# KKK_valdiklis_v3.net
KiCad netlist of a schematic drawn in EAGLE
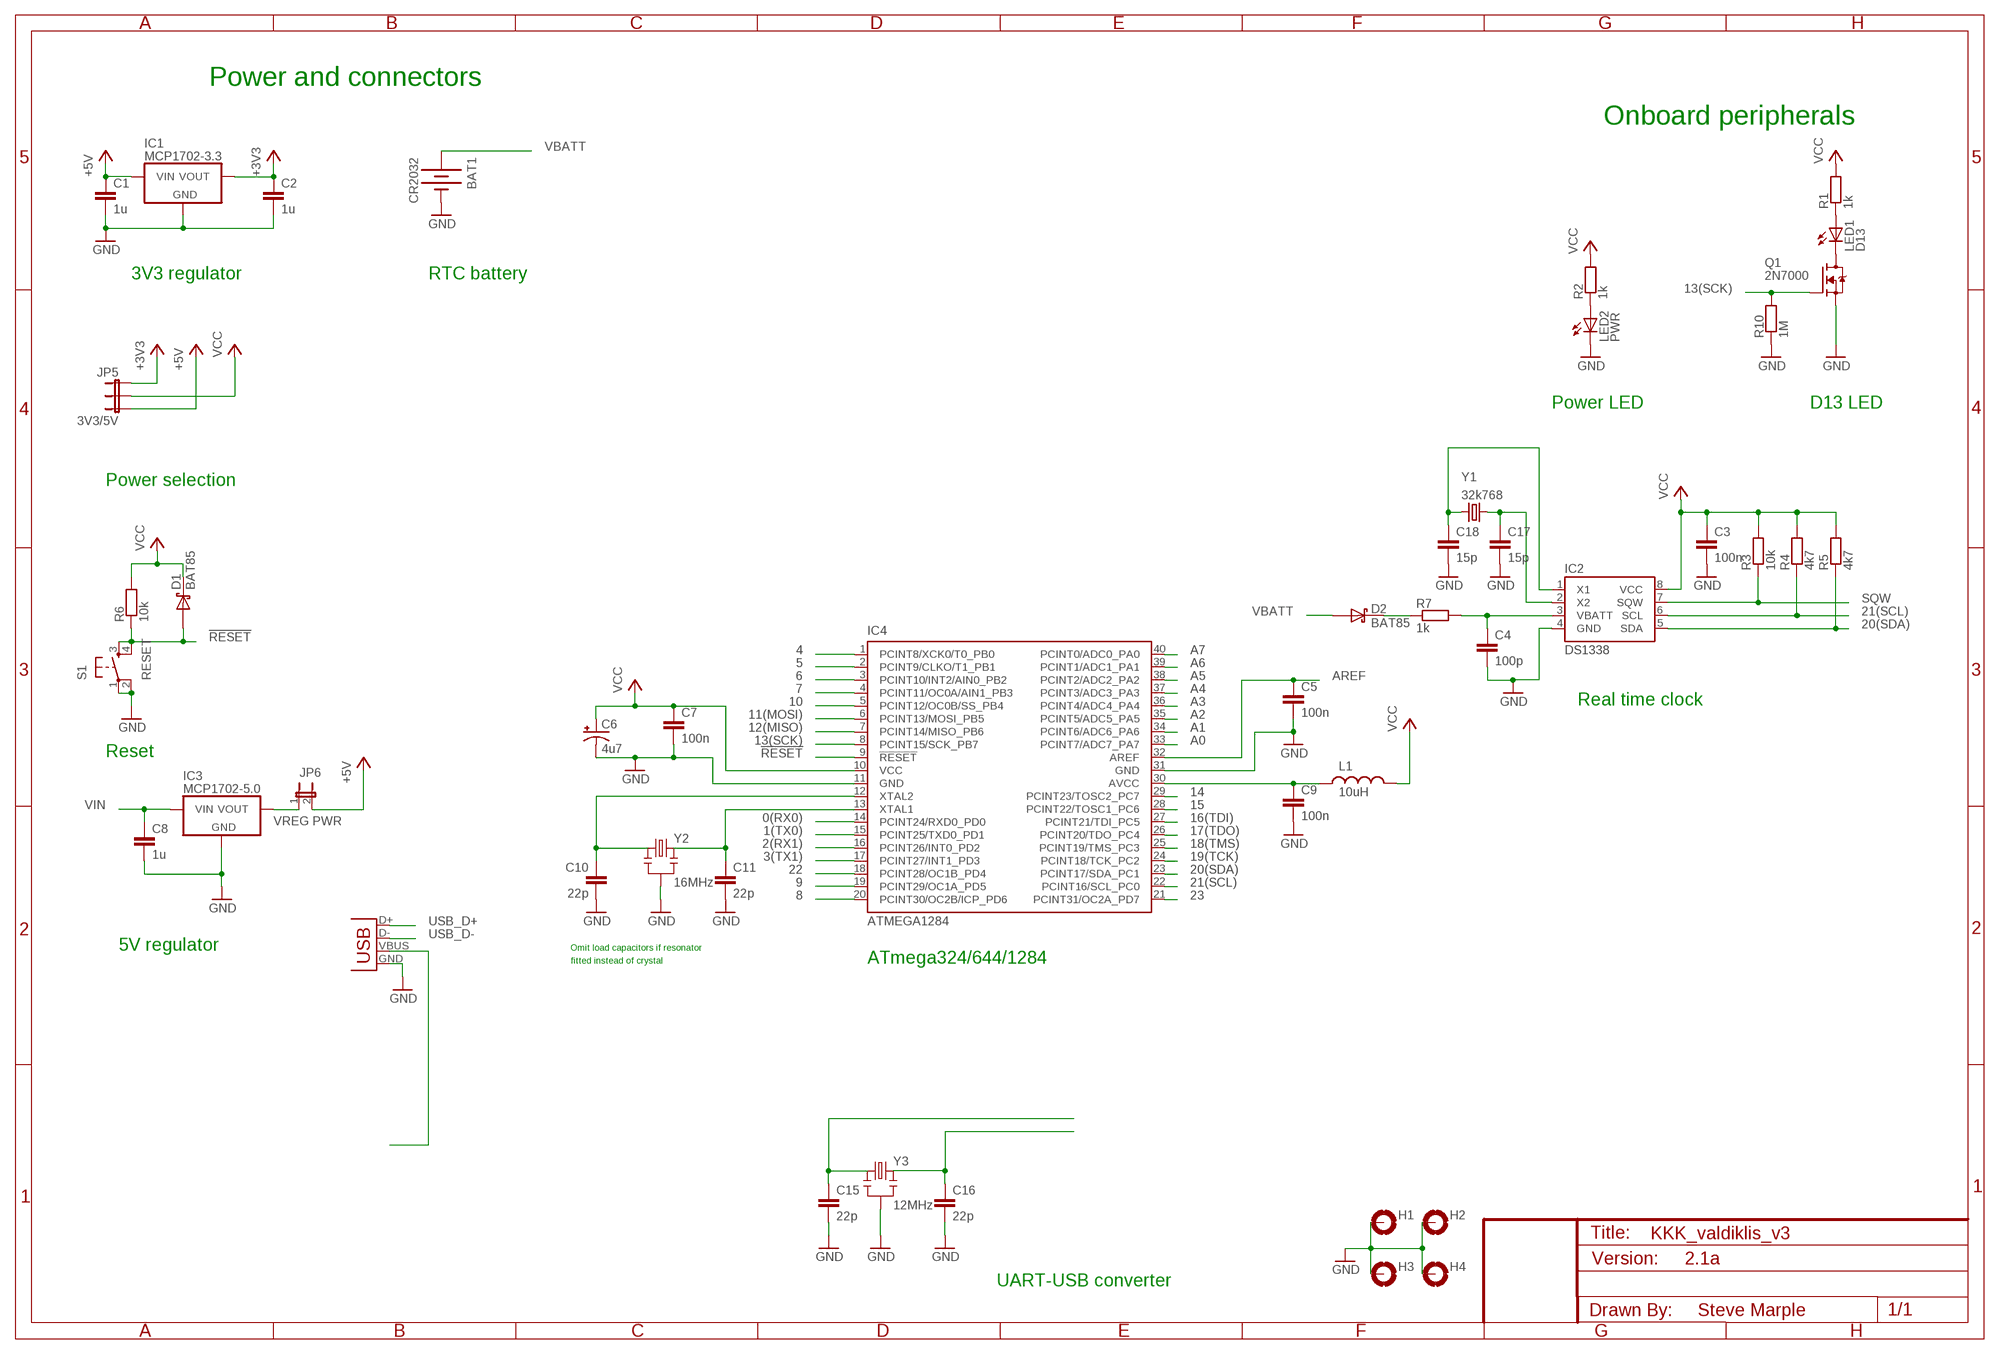
[diagram p0: schematic, sheet 1]

(export (version "E")
  (design (tool "Eeschema 10.0.6"))
  (components
    (comp (ref "BAT1")
      (value "CR2032")
      (footprint "eagle-import:BATTCOM_20MM_PTH")
      (libsource (lib "eagle-import") (part "BATTERY20PTH"))
    )
    (comp (ref "C1")
      (value "1u")
      (footprint "eagle-import:CAP-PTH-5MM")
      (libsource (lib "eagle-import") (part "CAPPTH1"))
    )
    (comp (ref "C2")
      (value "1u")
      (footprint "eagle-import:CAP-PTH-5MM")
      (libsource (lib "eagle-import") (part "CAPPTH1"))
    )
    (comp (ref "C3")
      (value "100n")
      (footprint "eagle-import:CAP-PTH-SMALL")
      (libsource (lib "eagle-import") (part "CAPPTH"))
    )
    (comp (ref "C4")
      (value "100p")
      (footprint "eagle-import:CAP-PTH-SMALL")
      (libsource (lib "eagle-import") (part "CAPPTH"))
    )
    (comp (ref "C5")
      (value "100n")
      (footprint "eagle-import:CAP-PTH-SMALL")
      (libsource (lib "eagle-import") (part "CAPPTH"))
    )
    (comp (ref "C6")
      (value "4u7")
      (footprint "eagle-import:CPOL-RADIAL-10UF-25V")
      (libsource (lib "eagle-import") (part "CAP_POLPTH2"))
    )
    (comp (ref "C7")
      (value "100n")
      (footprint "eagle-import:CAP-PTH-SMALL")
      (libsource (lib "eagle-import") (part "CAPPTH"))
    )
    (comp (ref "C8")
      (value "1u")
      (footprint "eagle-import:CAP-PTH-5MM")
      (libsource (lib "eagle-import") (part "CAPPTH1"))
    )
    (comp (ref "C9")
      (value "100n")
      (footprint "eagle-import:CAP-PTH-SMALL")
      (libsource (lib "eagle-import") (part "CAPPTH"))
    )
    (comp (ref "C10")
      (value "22p")
      (footprint "eagle-import:CAP-PTH-SMALL")
      (libsource (lib "eagle-import") (part "CAPPTH"))
    )
    (comp (ref "C11")
      (value "22p")
      (footprint "eagle-import:CAP-PTH-SMALL")
      (libsource (lib "eagle-import") (part "CAPPTH"))
    )
    (comp (ref "C15")
      (value "22p")
      (footprint "eagle-import:CAP-PTH-SMALL")
      (libsource (lib "eagle-import") (part "CAPPTH"))
    )
    (comp (ref "C16")
      (value "22p")
      (footprint "eagle-import:CAP-PTH-SMALL")
      (libsource (lib "eagle-import") (part "CAPPTH"))
    )
    (comp (ref "C17")
      (value "15p")
      (footprint "eagle-import:CAP-PTH-SMALL")
      (libsource (lib "eagle-import") (part "CAPPTH"))
    )
    (comp (ref "C18")
      (value "15p")
      (footprint "eagle-import:CAP-PTH-SMALL")
      (libsource (lib "eagle-import") (part "CAPPTH"))
    )
    (comp (ref "D1")
      (value "BAT85")
      (footprint "eagle-import:DIODE-TH-0.4")
      (libsource (lib "eagle-import") (part "DIODE-SCHOTTKY"))
    )
    (comp (ref "D2")
      (value "BAT85")
      (footprint "eagle-import:DIODE-TH-0.4")
      (libsource (lib "eagle-import") (part "DIODE-SCHOTTKY"))
    )
    (comp (ref "H1")
      (value "MOUNT-PAD-ROUND3.0")
      (footprint "eagle-import:3,0-PAD")
      (libsource (lib "eagle-import") (part "MOUNT-PAD-ROUND3.0"))
    )
    (comp (ref "H2")
      (value "MOUNT-PAD-ROUND3.0")
      (footprint "eagle-import:3,0-PAD")
      (libsource (lib "eagle-import") (part "MOUNT-PAD-ROUND3.0"))
    )
    (comp (ref "H3")
      (value "MOUNT-PAD-ROUND3.0")
      (footprint "eagle-import:3,0-PAD")
      (libsource (lib "eagle-import") (part "MOUNT-PAD-ROUND3.0"))
    )
    (comp (ref "H4")
      (value "MOUNT-PAD-ROUND3.0")
      (footprint "eagle-import:3,0-PAD")
      (libsource (lib "eagle-import") (part "MOUNT-PAD-ROUND3.0"))
    )
    (comp (ref "IC1")
      (value "MCP1702-3.3")
      (footprint "eagle-import:TO-92")
      (libsource (lib "eagle-import") (part "MCP1702"))
    )
    (comp (ref "IC2")
      (value "DS1338")
      (footprint "eagle-import:SO08")
      (libsource (lib "eagle-import") (part "DS1307SO08"))
    )
    (comp (ref "IC3")
      (value "MCP1702-5.0")
      (footprint "eagle-import:TO-92")
      (libsource (lib "eagle-import") (part "MCP1702"))
    )
    (comp (ref "IC4")
      (value "ATMEGA1284")
      (footprint "eagle-import:DIL40")
      (fields (field (name "MPN") "ATMEGA644-20PU"))
      (libsource (lib "eagle-import") (part "ATMEGA644-PU20"))
    )
    (comp (ref "JP5")
      (value "3V3/5V")
      (footprint "eagle-import:1X03")
      (libsource (lib "eagle-import") (part "JUMPER-3PTH"))
    )
    (comp (ref "JP6")
      (value "VREG PWR")
      (footprint "eagle-import:1X02")
      (libsource (lib "eagle-import") (part "JUMPER-2PTH"))
    )
    (comp (ref "L1")
      (value "10uH")
      (footprint "eagle-import:RES-AXIAL-0.4")
      (libsource (lib "eagle-import") (part "INDUCTOR0.4{dblquote}-AXIAL"))
    )
    (comp (ref "LED1")
      (value "D13")
      (footprint "eagle-import:LED3MM")
      (libsource (lib "eagle-import") (part "LED3MM"))
    )
    (comp (ref "LED2")
      (value "PWR")
      (footprint "eagle-import:LED3MM")
      (libsource (lib "eagle-import") (part "LED3MM"))
    )
    (comp (ref "Q1")
      (value "2N7000")
      (footprint "eagle-import:TO-92")
      (libsource (lib "eagle-import") (part "2N7000"))
    )
    (comp (ref "R1")
      (value "1k")
      (footprint "eagle-import:RES-AXIAL-0.4")
      (libsource (lib "eagle-import") (part "RESISTOR"))
    )
    (comp (ref "R2")
      (value "1k")
      (footprint "eagle-import:RES-AXIAL-0.4")
      (libsource (lib "eagle-import") (part "RESISTOR"))
    )
    (comp (ref "R3")
      (value "10k")
      (footprint "eagle-import:RES-AXIAL-0.4")
      (libsource (lib "eagle-import") (part "RESISTOR"))
    )
    (comp (ref "R4")
      (value "4k7")
      (footprint "eagle-import:RES-AXIAL-0.4")
      (libsource (lib "eagle-import") (part "RESISTOR"))
    )
    (comp (ref "R5")
      (value "4k7")
      (footprint "eagle-import:RES-AXIAL-0.4")
      (libsource (lib "eagle-import") (part "RESISTOR"))
    )
    (comp (ref "R6")
      (value "10k")
      (footprint "eagle-import:RES-AXIAL-0.4")
      (libsource (lib "eagle-import") (part "RESISTOR"))
    )
    (comp (ref "R7")
      (value "1k")
      (footprint "eagle-import:RES-AXIAL-0.4")
      (libsource (lib "eagle-import") (part "RESISTOR"))
    )
    (comp (ref "R10")
      (value "1M")
      (footprint "eagle-import:RES-AXIAL-0.4")
      (libsource (lib "eagle-import") (part "RESISTOR"))
    )
    (comp (ref "S1")
      (value "RESET")
      (footprint "eagle-import:TACTILE-PTH")
      (libsource (lib "eagle-import") (part "TAC_SWITCHPTH"))
    )
    (comp (ref "X3")
      (value "USB")
      (footprint "eagle-import:USB-B-PTH")
      (libsource (lib "eagle-import") (part "USBPTH"))
    )
    (comp (ref "Y1")
      (value "32k768")
      (footprint "eagle-import:TC38H")
      (libsource (lib "eagle-import") (part "CRYSTALTC38H"))
    )
    (comp (ref "Y2")
      (value "16MHz")
      (footprint "eagle-import:HC49U-V-RESONATOR")
      (libsource (lib "eagle-import") (part "CRYSTAL-RESONATOR"))
    )
    (comp (ref "Y3")
      (value "12MHz")
      (footprint "eagle-import:HC49U-V-RESONATOR")
      (libsource (lib "eagle-import") (part "CRYSTAL-RESONATOR"))
    )
  )
  (nets
    (net (code "1") (name "+3V3") (class "Default")
      (node (ref "C2") (pin "1") (pinfunction "1_1") (pintype "passive"))
      (node (ref "IC1") (pin "3") (pinfunction "VOUT_3") (pintype "passive"))
      (node (ref "JP5") (pin "1") (pinfunction "1_1") (pintype "passive"))
    )
    (net (code "2") (name "+5V") (class "Default")
      (node (ref "C1") (pin "1") (pinfunction "1_1") (pintype "passive"))
      (node (ref "IC1") (pin "2") (pinfunction "VIN_2") (pintype "input"))
      (node (ref "JP5") (pin "3") (pinfunction "3_3") (pintype "passive"))
      (node (ref "JP6") (pin "2") (pinfunction "2_2") (pintype "passive"))
    )
    (net (code "3") (name "/0(RX0)") (class "Default")
      (node (ref "IC4") (pin "14") (pinfunction "PCINT24/RXD0_PD0_14") (pintype "bidirectional"))
    )
    (net (code "4") (name "/1(TX0)") (class "Default")
      (node (ref "IC4") (pin "15") (pinfunction "PCINT25/TXD0_PD1_15") (pintype "bidirectional"))
    )
    (net (code "5") (name "/2(RX1)") (class "Default")
      (node (ref "IC4") (pin "16") (pinfunction "PCINT26/INT0_PD2_16") (pintype "bidirectional"))
    )
    (net (code "6") (name "/3(TX1)") (class "Default")
      (node (ref "IC4") (pin "17") (pinfunction "PCINT27/INT1_PD3_17") (pintype "bidirectional"))
    )
    (net (code "7") (name "/4") (class "Default")
      (node (ref "IC4") (pin "1") (pinfunction "PCINT8/XCK0/T0_PB0_1") (pintype "bidirectional"))
    )
    (net (code "8") (name "/5") (class "Default")
      (node (ref "IC4") (pin "2") (pinfunction "PCINT9/CLKO/T1_PB1_2") (pintype "bidirectional"))
    )
    (net (code "9") (name "/6") (class "Default")
      (node (ref "IC4") (pin "3") (pinfunction "PCINT10/INT2/AIN0_PB2_3") (pintype "bidirectional"))
    )
    (net (code "10") (name "/7") (class "Default")
      (node (ref "IC4") (pin "4") (pinfunction "PCINT11/OC0A/AIN1_PB3_4") (pintype "bidirectional"))
    )
    (net (code "11") (name "/8") (class "Default")
      (node (ref "IC4") (pin "20") (pinfunction "PCINT30/OC2B/ICP_PD6_20") (pintype "bidirectional"))
    )
    (net (code "12") (name "/9") (class "Default")
      (node (ref "IC4") (pin "19") (pinfunction "PCINT29/OC1A_PD5_19") (pintype "bidirectional"))
    )
    (net (code "13") (name "/10") (class "Default")
      (node (ref "IC4") (pin "5") (pinfunction "PCINT12/OC0B/SS_PB4_5") (pintype "bidirectional"))
    )
    (net (code "14") (name "/11(MOSI)") (class "Default")
      (node (ref "IC4") (pin "6") (pinfunction "PCINT13/MOSI_PB5_6") (pintype "bidirectional"))
    )
    (net (code "15") (name "/12(MISO)") (class "Default")
      (node (ref "IC4") (pin "7") (pinfunction "PCINT14/MISO_PB6_7") (pintype "bidirectional"))
    )
    (net (code "16") (name "/13(SCK)") (class "Default")
      (node (ref "IC4") (pin "8") (pinfunction "PCINT15/SCK_PB7_8") (pintype "bidirectional"))
      (node (ref "Q1") (pin "2") (pinfunction "G_2") (pintype "passive"))
      (node (ref "R10") (pin "P$2") (pinfunction "2_P$2") (pintype "passive"))
    )
    (net (code "17") (name "/14") (class "Default")
      (node (ref "IC4") (pin "29") (pinfunction "PCINT23/TOSC2_PC7_29") (pintype "bidirectional"))
    )
    (net (code "18") (name "/15") (class "Default")
      (node (ref "IC4") (pin "28") (pinfunction "PCINT22/TOSC1_PC6_28") (pintype "bidirectional"))
    )
    (net (code "19") (name "/16(TDI)") (class "Default")
      (node (ref "IC4") (pin "27") (pinfunction "PCINT21/TDI_PC5_27") (pintype "bidirectional"))
    )
    (net (code "20") (name "/17(TDO)") (class "Default")
      (node (ref "IC4") (pin "26") (pinfunction "PCINT20/TDO_PC4_26") (pintype "bidirectional"))
    )
    (net (code "21") (name "/18(TMS)") (class "Default")
      (node (ref "IC4") (pin "25") (pinfunction "PCINT19/TMS_PC3_25") (pintype "bidirectional"))
    )
    (net (code "22") (name "/19(TCK)") (class "Default")
      (node (ref "IC4") (pin "24") (pinfunction "PCINT18/TCK_PC2_24") (pintype "bidirectional"))
    )
    (net (code "23") (name "/20(SDA)") (class "Default")
      (node (ref "IC2") (pin "5") (pinfunction "SDA_5") (pintype "bidirectional"))
      (node (ref "IC4") (pin "23") (pinfunction "PCINT17/SDA_PC1_23") (pintype "bidirectional"))
      (node (ref "R5") (pin "P$1") (pinfunction "1_P$1") (pintype "passive"))
    )
    (net (code "24") (name "/21(SCL)") (class "Default")
      (node (ref "IC2") (pin "6") (pinfunction "SCL_6") (pintype "bidirectional"))
      (node (ref "IC4") (pin "22") (pinfunction "PCINT16/SCL_PC0_22") (pintype "bidirectional"))
      (node (ref "R4") (pin "P$1") (pinfunction "1_P$1") (pintype "passive"))
    )
    (net (code "25") (name "/22") (class "Default")
      (node (ref "IC4") (pin "18") (pinfunction "PCINT28/OC1B_PD4_18") (pintype "bidirectional"))
    )
    (net (code "26") (name "/23") (class "Default")
      (node (ref "IC4") (pin "21") (pinfunction "PCINT31/OC2A_PD7_21") (pintype "bidirectional"))
    )
    (net (code "27") (name "/A0") (class "Default")
      (node (ref "IC4") (pin "33") (pinfunction "PCINT7/ADC7_PA7_33") (pintype "bidirectional"))
    )
    (net (code "28") (name "/A1") (class "Default")
      (node (ref "IC4") (pin "34") (pinfunction "PCINT6/ADC6_PA6_34") (pintype "bidirectional"))
    )
    (net (code "29") (name "/A2") (class "Default")
      (node (ref "IC4") (pin "35") (pinfunction "PCINT5/ADC5_PA5_35") (pintype "bidirectional"))
    )
    (net (code "30") (name "/A3") (class "Default")
      (node (ref "IC4") (pin "36") (pinfunction "PCINT4/ADC4_PA4_36") (pintype "bidirectional"))
    )
    (net (code "31") (name "/A4") (class "Default")
      (node (ref "IC4") (pin "37") (pinfunction "PCINT3/ADC3_PA3_37") (pintype "bidirectional"))
    )
    (net (code "32") (name "/A5") (class "Default")
      (node (ref "IC4") (pin "38") (pinfunction "PCINT2/ADC2_PA2_38") (pintype "bidirectional"))
    )
    (net (code "33") (name "/A6") (class "Default")
      (node (ref "IC4") (pin "39") (pinfunction "PCINT1/ADC1_PA1_39") (pintype "bidirectional"))
    )
    (net (code "34") (name "/A7") (class "Default")
      (node (ref "IC4") (pin "40") (pinfunction "PCINT0/ADC0_PA0_40") (pintype "bidirectional"))
    )
    (net (code "35") (name "/AREF") (class "Default")
      (node (ref "C5") (pin "1") (pinfunction "1_1") (pintype "passive"))
      (node (ref "IC4") (pin "32") (pinfunction "AREF_32") (pintype "passive"))
    )
    (net (code "36") (name "/SQW") (class "Default")
      (node (ref "IC2") (pin "7") (pinfunction "SQW_7") (pintype "bidirectional"))
      (node (ref "R3") (pin "P$1") (pinfunction "1_P$1") (pintype "passive"))
    )
    (net (code "37") (name "/USB_D+") (class "Default")
      (node (ref "X3") (pin "D+") (pinfunction "D+_D+") (pintype "bidirectional"))
    )
    (net (code "38") (name "/USB_D-") (class "Default")
      (node (ref "X3") (pin "D-") (pinfunction "D-_D-") (pintype "bidirectional"))
    )
    (net (code "39") (name "/VBATT") (class "Default")
      (node (ref "BAT1") (pin "1") (pinfunction "+_1") (pintype "power_in"))
      (node (ref "D2") (pin "A") (pinfunction "A_A") (pintype "passive"))
    )
    (net (code "40") (name "/VIN") (class "Default")
      (node (ref "C8") (pin "1") (pinfunction "1_1") (pintype "passive"))
      (node (ref "IC3") (pin "2") (pinfunction "VIN_2") (pintype "input"))
    )
    (net (code "41") (name "/~{RESET}") (class "Default")
      (node (ref "D1") (pin "A") (pinfunction "A_A") (pintype "passive"))
      (node (ref "IC4") (pin "9") (pinfunction "~{RESET}_9") (pintype "input"))
      (node (ref "R6") (pin "P$1") (pinfunction "1_P$1") (pintype "passive"))
      (node (ref "S1") (pin "3") (pinfunction "3_3") (pintype "passive"))
      (node (ref "S1") (pin "4") (pinfunction "4_4") (pintype "passive"))
    )
    (net (code "42") (name "GND") (class "Default")
      (node (ref "BAT1") (pin "2") (pinfunction "-_2") (pintype "power_in"))
      (node (ref "C1") (pin "2") (pinfunction "2_2") (pintype "passive"))
      (node (ref "C10") (pin "2") (pinfunction "2_2") (pintype "passive"))
      (node (ref "C11") (pin "2") (pinfunction "2_2") (pintype "passive"))
      (node (ref "C15") (pin "2") (pinfunction "2_2") (pintype "passive"))
      (node (ref "C16") (pin "2") (pinfunction "2_2") (pintype "passive"))
      (node (ref "C17") (pin "2") (pinfunction "2_2") (pintype "passive"))
      (node (ref "C18") (pin "2") (pinfunction "2_2") (pintype "passive"))
      (node (ref "C2") (pin "2") (pinfunction "2_2") (pintype "passive"))
      (node (ref "C3") (pin "2") (pinfunction "2_2") (pintype "passive"))
      (node (ref "C4") (pin "2") (pinfunction "2_2") (pintype "passive"))
      (node (ref "C5") (pin "2") (pinfunction "2_2") (pintype "passive"))
      (node (ref "C6") (pin "2") (pinfunction "-_2") (pintype "passive"))
      (node (ref "C7") (pin "2") (pinfunction "2_2") (pintype "passive"))
      (node (ref "C8") (pin "2") (pinfunction "2_2") (pintype "passive"))
      (node (ref "C9") (pin "2") (pinfunction "2_2") (pintype "passive"))
      (node (ref "H1") (pin "B3,0") (pinfunction "MOUNT_B3,0") (pintype "passive"))
      (node (ref "H2") (pin "B3,0") (pinfunction "MOUNT_B3,0") (pintype "passive"))
      (node (ref "H3") (pin "B3,0") (pinfunction "MOUNT_B3,0") (pintype "passive"))
      (node (ref "H4") (pin "B3,0") (pinfunction "MOUNT_B3,0") (pintype "passive"))
      (node (ref "IC1") (pin "1") (pinfunction "GND_1") (pintype "passive"))
      (node (ref "IC2") (pin "4") (pinfunction "GND_4") (pintype "bidirectional"))
      (node (ref "IC3") (pin "1") (pinfunction "GND_1") (pintype "passive"))
      (node (ref "IC4") (pin "11") (pinfunction "GND_11") (pintype "power_in"))
      (node (ref "IC4") (pin "31") (pinfunction "GND_31") (pintype "power_in"))
      (node (ref "LED2") (pin "K") (pinfunction "C_K") (pintype "passive"))
      (node (ref "Q1") (pin "1") (pinfunction "S_1") (pintype "passive"))
      (node (ref "R10") (pin "P$1") (pinfunction "1_P$1") (pintype "passive"))
      (node (ref "S1") (pin "1") (pinfunction "1_1") (pintype "passive"))
      (node (ref "S1") (pin "2") (pinfunction "2_2") (pintype "passive"))
      (node (ref "X3") (pin "GND") (pinfunction "GND_GND") (pintype "bidirectional"))
      (node (ref "Y2") (pin "GND") (pinfunction "2_GND") (pintype "passive"))
      (node (ref "Y3") (pin "GND") (pinfunction "2_GND") (pintype "passive"))
    )
    (net (code "43") (name "Net-(C15-Pad1)") (class "Default")
      (node (ref "C15") (pin "1") (pinfunction "1_1") (pintype "passive"))
      (node (ref "Y3") (pin "1") (pinfunction "1_1") (pintype "passive"))
    )
    (net (code "44") (name "Net-(IC2-VBATT)") (class "Default")
      (node (ref "C4") (pin "1") (pinfunction "1_1") (pintype "passive"))
      (node (ref "IC2") (pin "3") (pinfunction "VBATT_3") (pintype "bidirectional"))
      (node (ref "R7") (pin "P$2") (pinfunction "2_P$2") (pintype "passive"))
    )
    (net (code "45") (name "Net-(IC2-X1)") (class "Default")
      (node (ref "C18") (pin "1") (pinfunction "1_1") (pintype "passive"))
      (node (ref "IC2") (pin "1") (pinfunction "X1_1") (pintype "bidirectional"))
      (node (ref "Y1") (pin "2") (pinfunction "2_2") (pintype "passive"))
    )
    (net (code "46") (name "Net-(IC2-X2)") (class "Default")
      (node (ref "C17") (pin "1") (pinfunction "1_1") (pintype "passive"))
      (node (ref "IC2") (pin "2") (pinfunction "X2_2") (pintype "bidirectional"))
      (node (ref "Y1") (pin "1") (pinfunction "1_1") (pintype "passive"))
    )
    (net (code "47") (name "Net-(IC3-VOUT)") (class "Default")
      (node (ref "IC3") (pin "3") (pinfunction "VOUT_3") (pintype "passive"))
      (node (ref "JP6") (pin "1") (pinfunction "1_1") (pintype "passive"))
    )
    (net (code "48") (name "Net-(IC4-AVCC)") (class "Default")
      (node (ref "C9") (pin "1") (pinfunction "1_1") (pintype "passive"))
      (node (ref "IC4") (pin "30") (pinfunction "AVCC_30") (pintype "power_in"))
      (node (ref "L1") (pin "P$1") (pinfunction "1_P$1") (pintype "passive"))
    )
    (net (code "49") (name "Net-(IC4-XTAL1)") (class "Default")
      (node (ref "C11") (pin "1") (pinfunction "1_1") (pintype "passive"))
      (node (ref "IC4") (pin "13") (pinfunction "XTAL1_13") (pintype "input"))
      (node (ref "Y2") (pin "2") (pinfunction "3_2") (pintype "passive"))
    )
    (net (code "50") (name "Net-(IC4-XTAL2)") (class "Default")
      (node (ref "C10") (pin "1") (pinfunction "1_1") (pintype "passive"))
      (node (ref "IC4") (pin "12") (pinfunction "XTAL2_12") (pintype "output"))
      (node (ref "Y2") (pin "1") (pinfunction "1_1") (pintype "passive"))
    )
    (net (code "51") (name "Net-(LED1-C)") (class "Default")
      (node (ref "LED1") (pin "K") (pinfunction "C_K") (pintype "passive"))
      (node (ref "Q1") (pin "3") (pinfunction "D_3") (pintype "passive"))
    )
    (net (code "52") (name "Net-(R1-1)") (class "Default")
      (node (ref "LED1") (pin "A") (pinfunction "A_A") (pintype "passive"))
      (node (ref "R1") (pin "P$1") (pinfunction "1_P$1") (pintype "passive"))
    )
    (net (code "53") (name "Net-(R2-1)") (class "Default")
      (node (ref "LED2") (pin "A") (pinfunction "A_A") (pintype "passive"))
      (node (ref "R2") (pin "P$1") (pinfunction "1_P$1") (pintype "passive"))
    )
    (net (code "54") (name "Net-(R7-1)") (class "Default")
      (node (ref "D2") (pin "C") (pinfunction "C_C") (pintype "passive"))
      (node (ref "R7") (pin "P$1") (pinfunction "1_P$1") (pintype "passive"))
    )
    (net (code "55") (name "Net-(Y3-3)") (class "Default")
      (node (ref "C16") (pin "1") (pinfunction "1_1") (pintype "passive"))
      (node (ref "Y3") (pin "2") (pinfunction "3_2") (pintype "passive"))
    )
    (net (code "56") (name "VCC") (class "Default")
      (node (ref "C3") (pin "1") (pinfunction "1_1") (pintype "passive"))
      (node (ref "C6") (pin "1") (pinfunction "+_1") (pintype "passive"))
      (node (ref "C7") (pin "1") (pinfunction "1_1") (pintype "passive"))
      (node (ref "D1") (pin "C") (pinfunction "C_C") (pintype "passive"))
      (node (ref "IC2") (pin "8") (pinfunction "VCC_8") (pintype "bidirectional"))
      (node (ref "IC4") (pin "10") (pinfunction "VCC_10") (pintype "power_in"))
      (node (ref "JP5") (pin "2") (pinfunction "2_2") (pintype "passive"))
      (node (ref "L1") (pin "P$2") (pinfunction "2_P$2") (pintype "passive"))
      (node (ref "R1") (pin "P$2") (pinfunction "2_P$2") (pintype "passive"))
      (node (ref "R2") (pin "P$2") (pinfunction "2_P$2") (pintype "passive"))
      (node (ref "R3") (pin "P$2") (pinfunction "2_P$2") (pintype "passive"))
      (node (ref "R4") (pin "P$2") (pinfunction "2_P$2") (pintype "passive"))
      (node (ref "R5") (pin "P$2") (pinfunction "2_P$2") (pintype "passive"))
      (node (ref "R6") (pin "P$2") (pinfunction "2_P$2") (pintype "passive"))
    )
    (net (code "57") (name "unconnected-(X3-PadVBUS)") (class "Default")
      (node (ref "X3") (pin "VBUS") (pinfunction "VBUS_VBUS") (pintype "bidirectional"))
    )
  )
)
